# Pad_Pad_ecg.net
KiCad netlist of a schematic drawn in Altium Designer
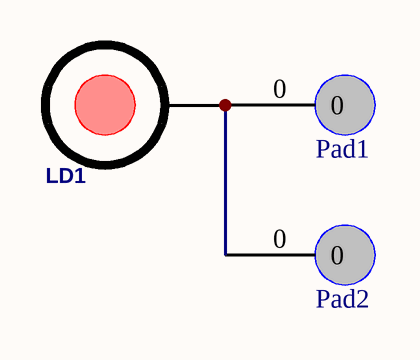
[diagram p0: [Pad]Pad_ecg.SchDoc]

(export (version "E")
  (design (tool "Eeschema 10.0.6"))
  (components
    (comp (ref "LD1")
      (value "ECG LEAD")
      (footprint "ECG PAD")
      (libsource (lib "VitalSignal EcgPpg Board") (part "ECG LEAD"))
    )
    (comp (ref "Pad1")
      (value "pad_ecg")
      (footprint "PcbLib1:pad_ecg")
      (libsource (lib "Schlib1") (part "pad_ecg"))
    )
    (comp (ref "Pad2")
      (value "pad_ecg")
      (footprint "PcbLib1:pad_ecg")
      (libsource (lib "Schlib1") (part "pad_ecg"))
    )
  )
  (nets
    (net (code "1") (name "Net-(LD1-Pad1)") (class "Default")
      (node (ref "LD1") (pin "1") (pinfunction "1_1") (pintype "passive"))
      (node (ref "Pad1") (pin "0") (pinfunction "0_0") (pintype "passive"))
      (node (ref "Pad2") (pin "0") (pinfunction "0_0") (pintype "passive"))
    )
  )
)
